# Sheet1.net
KiCad netlist of a schematic drawn in Altium Designer
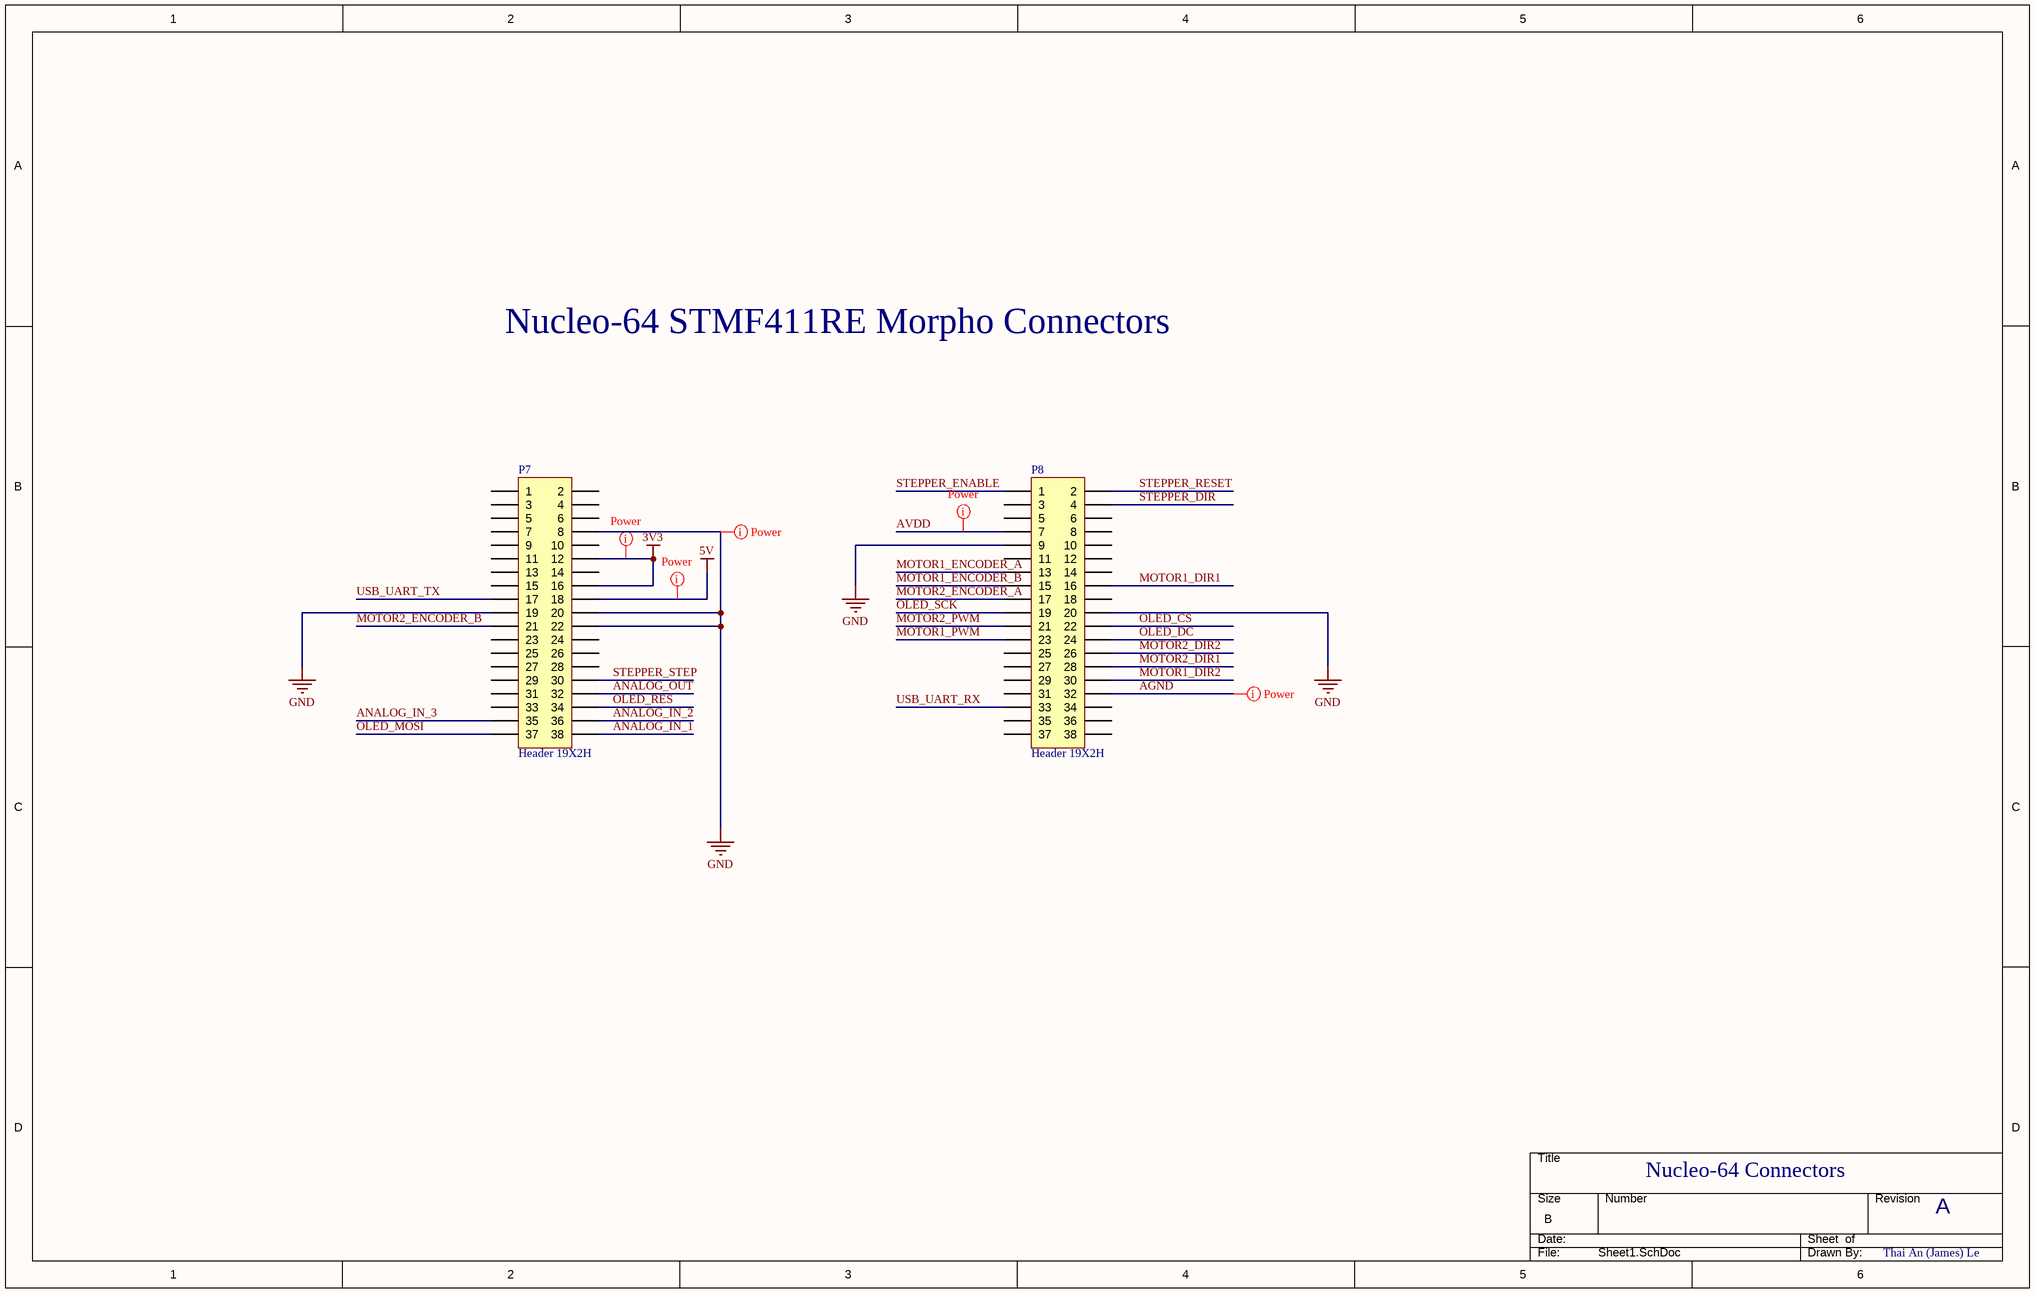
[diagram p0: Sheet1.SchDoc]

(export (version "E")
  (design (tool "Eeschema 10.0.6"))
  (components
    (comp (ref "P7")
      (value "Header 19X2H")
      (footprint "PPPC192LFBN-RC")
      (description "38 Position Header Connector 0.100in (2.54mm) Through Hole Gold")
      (fields (field (name "MPN") "PPPC192LFBN-RC"))
      (libsource (lib "esd_library") (part "Header 19X2H"))
    )
    (comp (ref "P8")
      (value "Header 19X2H")
      (footprint "PPPC192LFBN-RC")
      (description "38 Position Header Connector 0.100in (2.54mm) Through Hole Gold")
      (fields (field (name "MPN") "PPPC192LFBN-RC"))
      (libsource (lib "esd_library") (part "Header 19X2H"))
    )
  )
  (nets
    (net (code "1") (name "/AGND") (class "Default")
      (node (ref "P8") (pin "32") (pinfunction "32_32") (pintype "passive"))
    )
    (net (code "2") (name "/ANALOG_IN_1") (class "Default")
      (node (ref "P7") (pin "38") (pinfunction "38_38") (pintype "passive"))
    )
    (net (code "3") (name "/ANALOG_IN_2") (class "Default")
      (node (ref "P7") (pin "36") (pinfunction "36_36") (pintype "passive"))
    )
    (net (code "4") (name "/ANALOG_IN_3") (class "Default")
      (node (ref "P7") (pin "35") (pinfunction "35_35") (pintype "passive"))
    )
    (net (code "5") (name "/ANALOG_OUT") (class "Default")
      (node (ref "P7") (pin "32") (pinfunction "32_32") (pintype "passive"))
    )
    (net (code "6") (name "/AVDD") (class "Default")
      (node (ref "P8") (pin "7") (pinfunction "7_7") (pintype "passive"))
    )
    (net (code "7") (name "/MOTOR1_DIR1") (class "Default")
      (node (ref "P8") (pin "16") (pinfunction "16_16") (pintype "passive"))
    )
    (net (code "8") (name "/MOTOR1_DIR2") (class "Default")
      (node (ref "P8") (pin "30") (pinfunction "30_30") (pintype "passive"))
    )
    (net (code "9") (name "/MOTOR1_ENCODER_A") (class "Default")
      (node (ref "P8") (pin "13") (pinfunction "13_13") (pintype "passive"))
    )
    (net (code "10") (name "/MOTOR1_ENCODER_B") (class "Default")
      (node (ref "P8") (pin "15") (pinfunction "15_15") (pintype "passive"))
    )
    (net (code "11") (name "/MOTOR1_PWM") (class "Default")
      (node (ref "P8") (pin "23") (pinfunction "23_23") (pintype "passive"))
    )
    (net (code "12") (name "/MOTOR2_DIR1") (class "Default")
      (node (ref "P8") (pin "28") (pinfunction "28_28") (pintype "passive"))
    )
    (net (code "13") (name "/MOTOR2_DIR2") (class "Default")
      (node (ref "P8") (pin "26") (pinfunction "26_26") (pintype "passive"))
    )
    (net (code "14") (name "/MOTOR2_ENCODER_A") (class "Default")
      (node (ref "P8") (pin "17") (pinfunction "17_17") (pintype "passive"))
    )
    (net (code "15") (name "/MOTOR2_ENCODER_B") (class "Default")
      (node (ref "P7") (pin "21") (pinfunction "21_21") (pintype "passive"))
    )
    (net (code "16") (name "/MOTOR2_PWM") (class "Default")
      (node (ref "P8") (pin "21") (pinfunction "21_21") (pintype "passive"))
    )
    (net (code "17") (name "/OLED_CS") (class "Default")
      (node (ref "P8") (pin "22") (pinfunction "22_22") (pintype "passive"))
    )
    (net (code "18") (name "/OLED_DC") (class "Default")
      (node (ref "P8") (pin "24") (pinfunction "24_24") (pintype "passive"))
    )
    (net (code "19") (name "/OLED_MOSI") (class "Default")
      (node (ref "P7") (pin "37") (pinfunction "37_37") (pintype "passive"))
    )
    (net (code "20") (name "/OLED_RES") (class "Default")
      (node (ref "P7") (pin "34") (pinfunction "34_34") (pintype "passive"))
    )
    (net (code "21") (name "/OLED_SCK") (class "Default")
      (node (ref "P8") (pin "19") (pinfunction "19_19") (pintype "passive"))
    )
    (net (code "22") (name "/STEPPER_DIR") (class "Default")
      (node (ref "P8") (pin "4") (pinfunction "4_4") (pintype "passive"))
    )
    (net (code "23") (name "/STEPPER_ENABLE") (class "Default")
      (node (ref "P8") (pin "1") (pinfunction "1_1") (pintype "passive"))
    )
    (net (code "24") (name "/STEPPER_RESET") (class "Default")
      (node (ref "P8") (pin "2") (pinfunction "2_2") (pintype "passive"))
    )
    (net (code "25") (name "/STEPPER_STEP") (class "Default")
      (node (ref "P7") (pin "30") (pinfunction "30_30") (pintype "passive"))
    )
    (net (code "26") (name "/USB_UART_RX") (class "Default")
      (node (ref "P8") (pin "33") (pinfunction "33_33") (pintype "passive"))
    )
    (net (code "27") (name "/USB_UART_TX") (class "Default")
      (node (ref "P7") (pin "17") (pinfunction "17_17") (pintype "passive"))
    )
    (net (code "28") (name "3V3") (class "Default")
      (node (ref "P7") (pin "12") (pinfunction "12_12") (pintype "passive"))
      (node (ref "P7") (pin "16") (pinfunction "16_16") (pintype "passive"))
    )
    (net (code "29") (name "5V") (class "Default")
      (node (ref "P7") (pin "18") (pinfunction "18_18") (pintype "passive"))
    )
    (net (code "30") (name "GND") (class "Default")
      (node (ref "P7") (pin "19") (pinfunction "19_19") (pintype "passive"))
      (node (ref "P7") (pin "20") (pinfunction "20_20") (pintype "passive"))
      (node (ref "P7") (pin "22") (pinfunction "22_22") (pintype "passive"))
      (node (ref "P7") (pin "8") (pinfunction "8_8") (pintype "passive"))
      (node (ref "P8") (pin "20") (pinfunction "20_20") (pintype "passive"))
      (node (ref "P8") (pin "9") (pinfunction "9_9") (pintype "passive"))
    )
    (net (code "31") (name "unconnected-(P7-Pad1)") (class "Default")
      (node (ref "P7") (pin "1") (pinfunction "1_1") (pintype "passive"))
    )
    (net (code "32") (name "unconnected-(P7-Pad2)") (class "Default")
      (node (ref "P7") (pin "2") (pinfunction "2_2") (pintype "passive"))
    )
    (net (code "33") (name "unconnected-(P7-Pad3)") (class "Default")
      (node (ref "P7") (pin "3") (pinfunction "3_3") (pintype "passive"))
    )
    (net (code "34") (name "unconnected-(P7-Pad4)") (class "Default")
      (node (ref "P7") (pin "4") (pinfunction "4_4") (pintype "passive"))
    )
    (net (code "35") (name "unconnected-(P7-Pad5)") (class "Default")
      (node (ref "P7") (pin "5") (pinfunction "5_5") (pintype "passive"))
    )
    (net (code "36") (name "unconnected-(P7-Pad6)") (class "Default")
      (node (ref "P7") (pin "6") (pinfunction "6_6") (pintype "passive"))
    )
    (net (code "37") (name "unconnected-(P7-Pad7)") (class "Default")
      (node (ref "P7") (pin "7") (pinfunction "7_7") (pintype "passive"))
    )
    (net (code "38") (name "unconnected-(P7-Pad9)") (class "Default")
      (node (ref "P7") (pin "9") (pinfunction "9_9") (pintype "passive"))
    )
    (net (code "39") (name "unconnected-(P7-Pad10)") (class "Default")
      (node (ref "P7") (pin "10") (pinfunction "10_10") (pintype "passive"))
    )
    (net (code "40") (name "unconnected-(P7-Pad11)") (class "Default")
      (node (ref "P7") (pin "11") (pinfunction "11_11") (pintype "passive"))
    )
    (net (code "41") (name "unconnected-(P7-Pad13)") (class "Default")
      (node (ref "P7") (pin "13") (pinfunction "13_13") (pintype "passive"))
    )
    (net (code "42") (name "unconnected-(P7-Pad14)") (class "Default")
      (node (ref "P7") (pin "14") (pinfunction "14_14") (pintype "passive"))
    )
    (net (code "43") (name "unconnected-(P7-Pad15)") (class "Default")
      (node (ref "P7") (pin "15") (pinfunction "15_15") (pintype "passive"))
    )
    (net (code "44") (name "unconnected-(P7-Pad23)") (class "Default")
      (node (ref "P7") (pin "23") (pinfunction "23_23") (pintype "passive"))
    )
    (net (code "45") (name "unconnected-(P7-Pad24)") (class "Default")
      (node (ref "P7") (pin "24") (pinfunction "24_24") (pintype "passive"))
    )
    (net (code "46") (name "unconnected-(P7-Pad25)") (class "Default")
      (node (ref "P7") (pin "25") (pinfunction "25_25") (pintype "passive"))
    )
    (net (code "47") (name "unconnected-(P7-Pad26)") (class "Default")
      (node (ref "P7") (pin "26") (pinfunction "26_26") (pintype "passive"))
    )
    (net (code "48") (name "unconnected-(P7-Pad27)") (class "Default")
      (node (ref "P7") (pin "27") (pinfunction "27_27") (pintype "passive"))
    )
    (net (code "49") (name "unconnected-(P7-Pad28)") (class "Default")
      (node (ref "P7") (pin "28") (pinfunction "28_28") (pintype "passive"))
    )
    (net (code "50") (name "unconnected-(P7-Pad29)") (class "Default")
      (node (ref "P7") (pin "29") (pinfunction "29_29") (pintype "passive"))
    )
    (net (code "51") (name "unconnected-(P7-Pad31)") (class "Default")
      (node (ref "P7") (pin "31") (pinfunction "31_31") (pintype "passive"))
    )
    (net (code "52") (name "unconnected-(P7-Pad33)") (class "Default")
      (node (ref "P7") (pin "33") (pinfunction "33_33") (pintype "passive"))
    )
    (net (code "53") (name "unconnected-(P8-Pad3)") (class "Default")
      (node (ref "P8") (pin "3") (pinfunction "3_3") (pintype "passive"))
    )
    (net (code "54") (name "unconnected-(P8-Pad5)") (class "Default")
      (node (ref "P8") (pin "5") (pinfunction "5_5") (pintype "passive"))
    )
    (net (code "55") (name "unconnected-(P8-Pad6)") (class "Default")
      (node (ref "P8") (pin "6") (pinfunction "6_6") (pintype "passive"))
    )
    (net (code "56") (name "unconnected-(P8-Pad8)") (class "Default")
      (node (ref "P8") (pin "8") (pinfunction "8_8") (pintype "passive"))
    )
    (net (code "57") (name "unconnected-(P8-Pad10)") (class "Default")
      (node (ref "P8") (pin "10") (pinfunction "10_10") (pintype "passive"))
    )
    (net (code "58") (name "unconnected-(P8-Pad11)") (class "Default")
      (node (ref "P8") (pin "11") (pinfunction "11_11") (pintype "passive"))
    )
    (net (code "59") (name "unconnected-(P8-Pad12)") (class "Default")
      (node (ref "P8") (pin "12") (pinfunction "12_12") (pintype "passive"))
    )
    (net (code "60") (name "unconnected-(P8-Pad14)") (class "Default")
      (node (ref "P8") (pin "14") (pinfunction "14_14") (pintype "passive"))
    )
    (net (code "61") (name "unconnected-(P8-Pad18)") (class "Default")
      (node (ref "P8") (pin "18") (pinfunction "18_18") (pintype "passive"))
    )
    (net (code "62") (name "unconnected-(P8-Pad25)") (class "Default")
      (node (ref "P8") (pin "25") (pinfunction "25_25") (pintype "passive"))
    )
    (net (code "63") (name "unconnected-(P8-Pad27)") (class "Default")
      (node (ref "P8") (pin "27") (pinfunction "27_27") (pintype "passive"))
    )
    (net (code "64") (name "unconnected-(P8-Pad29)") (class "Default")
      (node (ref "P8") (pin "29") (pinfunction "29_29") (pintype "passive"))
    )
    (net (code "65") (name "unconnected-(P8-Pad31)") (class "Default")
      (node (ref "P8") (pin "31") (pinfunction "31_31") (pintype "passive"))
    )
    (net (code "66") (name "unconnected-(P8-Pad34)") (class "Default")
      (node (ref "P8") (pin "34") (pinfunction "34_34") (pintype "passive"))
    )
    (net (code "67") (name "unconnected-(P8-Pad35)") (class "Default")
      (node (ref "P8") (pin "35") (pinfunction "35_35") (pintype "passive"))
    )
    (net (code "68") (name "unconnected-(P8-Pad36)") (class "Default")
      (node (ref "P8") (pin "36") (pinfunction "36_36") (pintype "passive"))
    )
    (net (code "69") (name "unconnected-(P8-Pad37)") (class "Default")
      (node (ref "P8") (pin "37") (pinfunction "37_37") (pintype "passive"))
    )
    (net (code "70") (name "unconnected-(P8-Pad38)") (class "Default")
      (node (ref "P8") (pin "38") (pinfunction "38_38") (pintype "passive"))
    )
  )
)
